# R-2R_Ladder_V2.net
KiCad netlist of a schematic drawn in EasyEDA
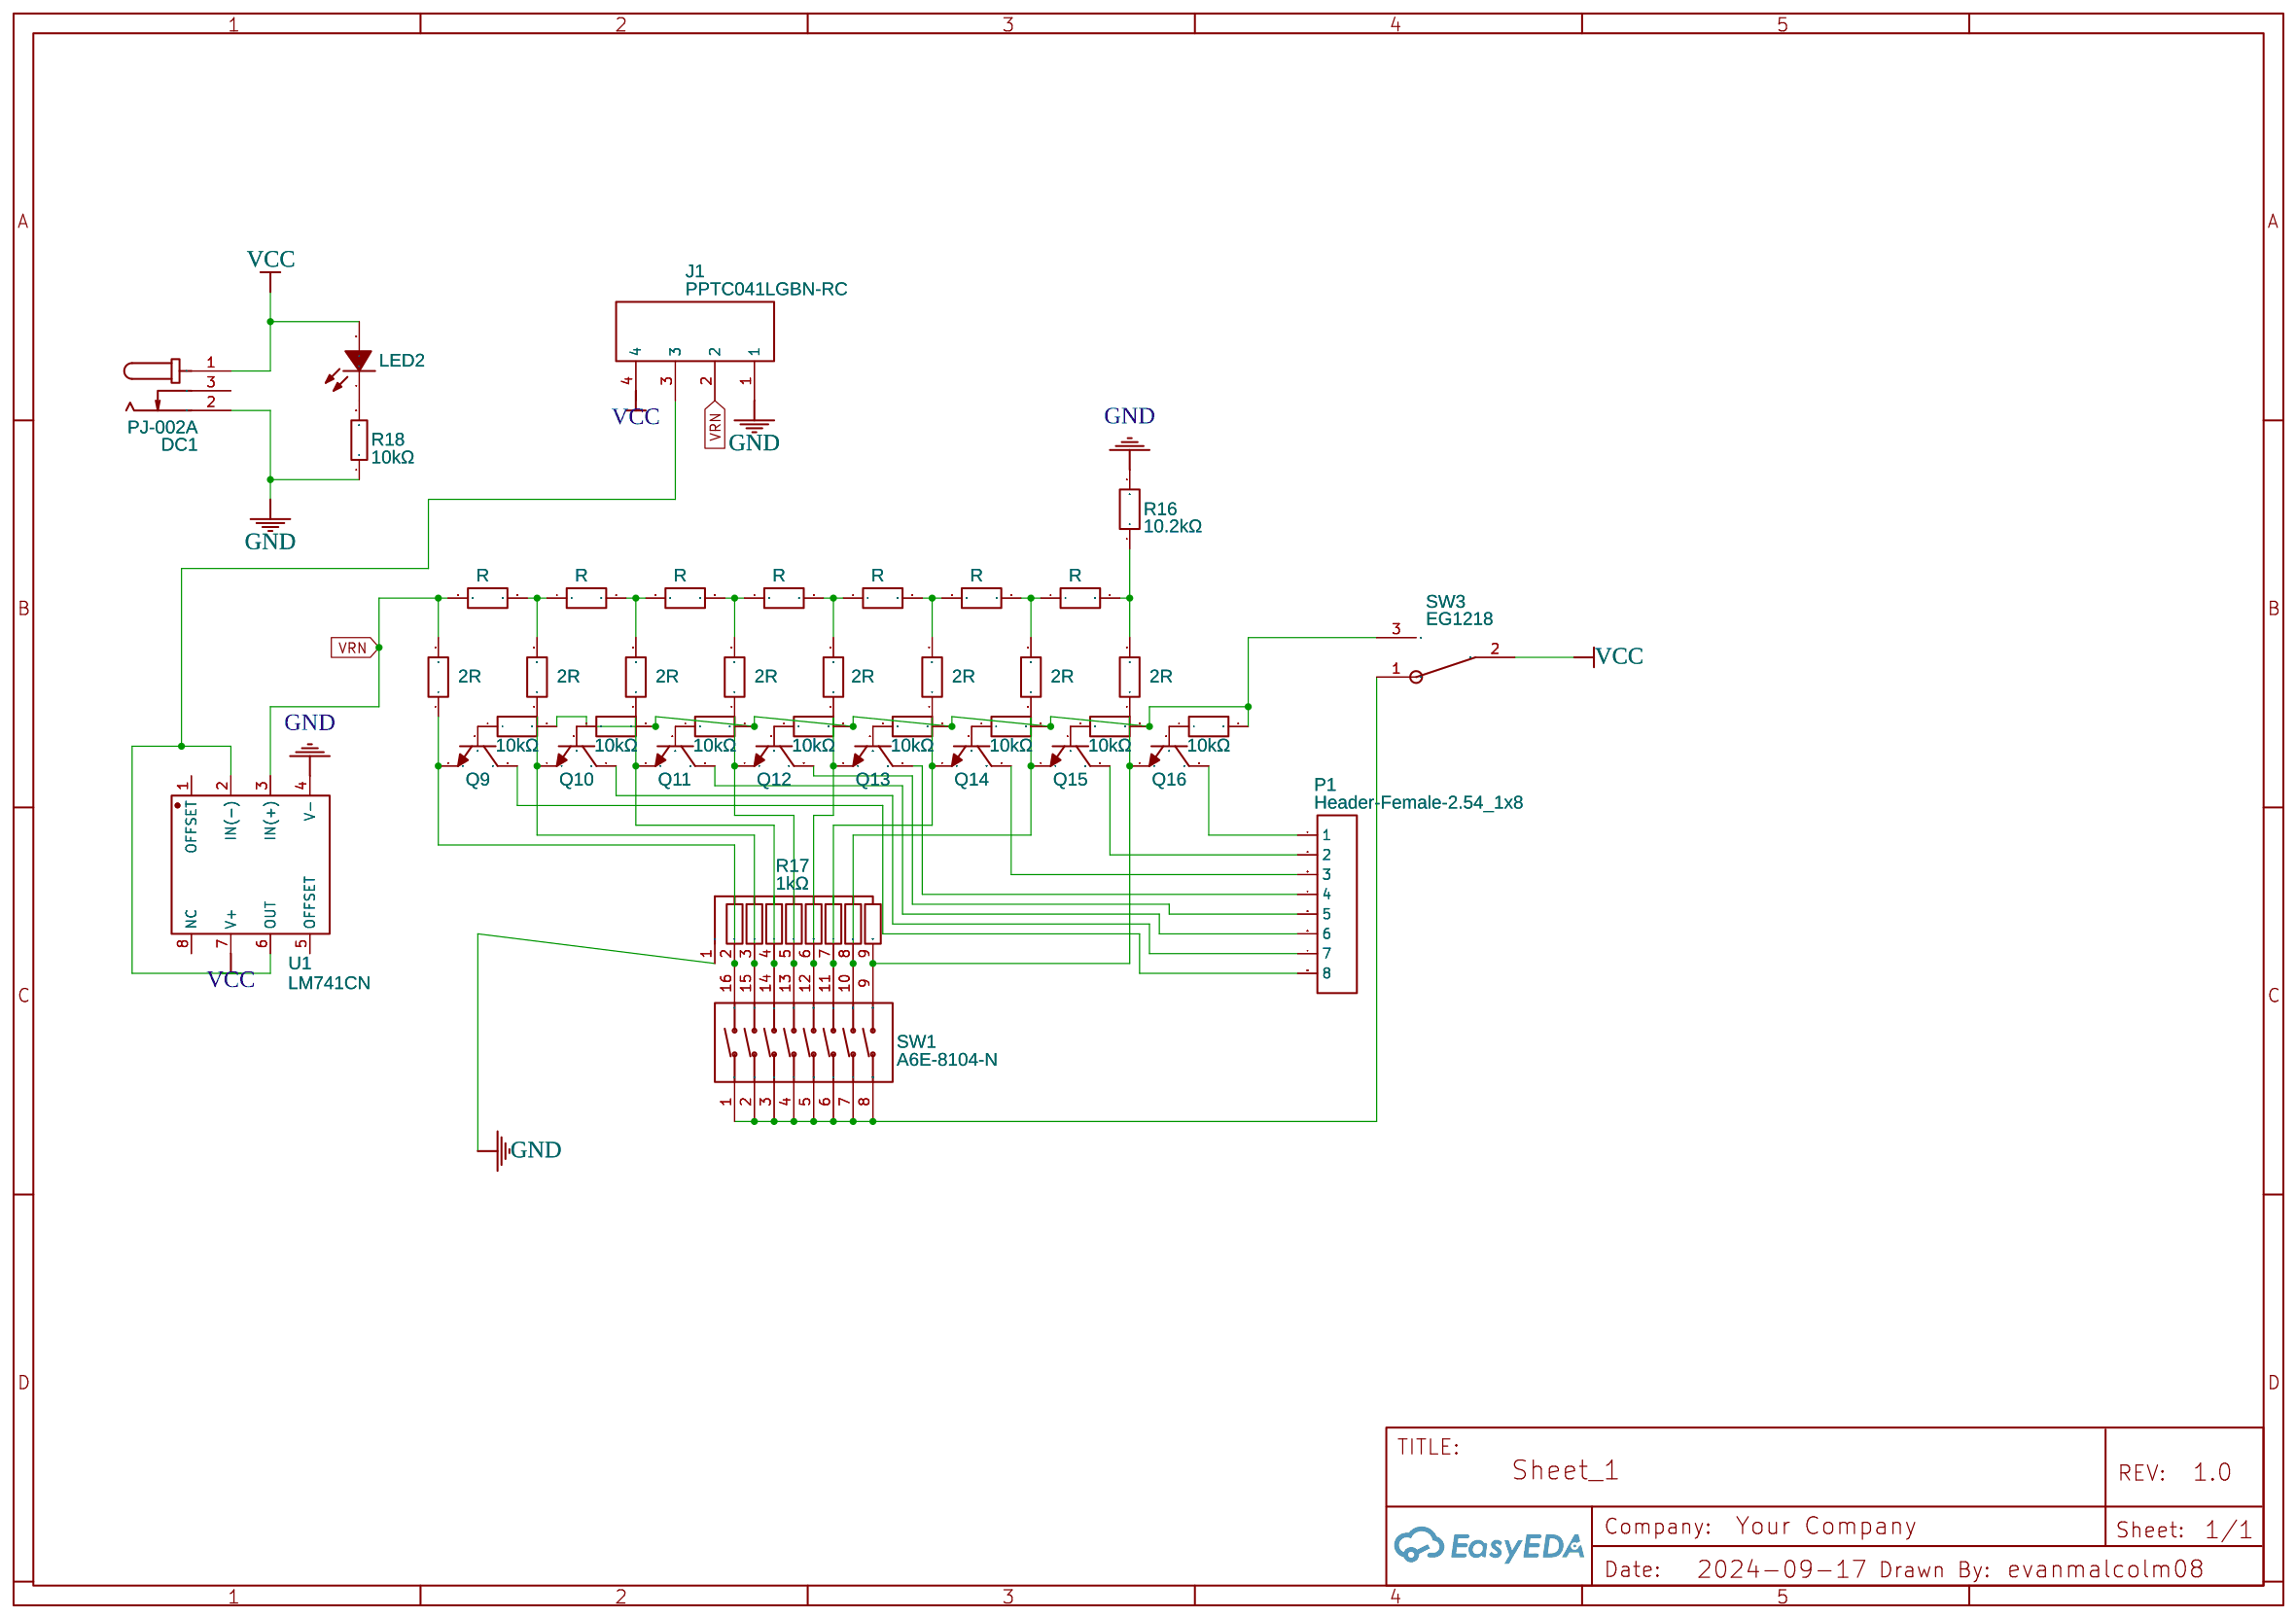
[diagram p0: schematic sheet]

(export (version "E")
  (design (tool "Eeschema 10.0.6"))
  (components
    (comp (ref "DC1")
      (value "PJ-002A")
      (fields (field (name "Manufacturer") "CUI"))
      (libsource (lib "") (part "PJ-002A"))
    )
    (comp (ref "J1") (value "PPTC041LGBN-RC") (libsource (lib "") (part "PPTC041LGBN-RC")))
    (comp (ref "LED2")
      (value "LTST-C150TBKT")
      (fields (field (name "Manufacturer") "LITEON(光宝)"))
      (libsource (lib "") (part "LTST-C150TBKT"))
    )
    (comp (ref "P1")
      (value "Header-Female-2.54_1x8")
      (fields (field (name "Manufacturer Part") "2.54-1*8P母环保") (field (name "Manufacturer") "BOOMELE(博穆精密)"))
      (libsource (lib "") (part "Header-Female-2.54_1x8"))
    )
    (comp (ref "Q9")
      (value "2N3904TF")
      (fields (field (name "Manufacturer") "onsemi(安森美)"))
      (libsource (lib "") (part "2N3904TF"))
    )
    (comp (ref "Q10")
      (value "2N3904TF")
      (fields (field (name "Manufacturer") "onsemi(安森美)"))
      (libsource (lib "") (part "2N3904TF"))
    )
    (comp (ref "Q11")
      (value "2N3904TF")
      (fields (field (name "Manufacturer") "onsemi(安森美)"))
      (libsource (lib "") (part "2N3904TF"))
    )
    (comp (ref "Q12")
      (value "2N3904TF")
      (fields (field (name "Manufacturer") "onsemi(安森美)"))
      (libsource (lib "") (part "2N3904TF"))
    )
    (comp (ref "Q13")
      (value "2N3904TF")
      (fields (field (name "Manufacturer") "onsemi(安森美)"))
      (libsource (lib "") (part "2N3904TF"))
    )
    (comp (ref "Q14")
      (value "2N3904TF")
      (fields (field (name "Manufacturer") "onsemi(安森美)"))
      (libsource (lib "") (part "2N3904TF"))
    )
    (comp (ref "Q15")
      (value "2N3904TF")
      (fields (field (name "Manufacturer") "onsemi(安森美)"))
      (libsource (lib "") (part "2N3904TF"))
    )
    (comp (ref "Q16")
      (value "2N3904TF")
      (fields (field (name "Manufacturer") "onsemi(安森美)"))
      (libsource (lib "") (part "2N3904TF"))
    )
    (comp (ref "R1")
      (value "R")
      (fields
        (field (name "Manufacturer Part") "CF14JT10K0")
        (field (name "Manufacturer") "SEI(Stackpole Electronics Inc.)")
      )
      (libsource (lib "") (part "CF14JT10K0"))
    )
    (comp (ref "R2")
      (value "R")
      (fields
        (field (name "Manufacturer Part") "CF14JT10K0")
        (field (name "Manufacturer") "SEI(Stackpole Electronics Inc.)")
      )
      (libsource (lib "") (part "CF14JT10K0"))
    )
    (comp (ref "R3")
      (value "R")
      (fields
        (field (name "Manufacturer Part") "CF14JT10K0")
        (field (name "Manufacturer") "SEI(Stackpole Electronics Inc.)")
      )
      (libsource (lib "") (part "CF14JT10K0"))
    )
    (comp (ref "R4")
      (value "R")
      (fields
        (field (name "Manufacturer Part") "CF14JT10K0")
        (field (name "Manufacturer") "SEI(Stackpole Electronics Inc.)")
      )
      (libsource (lib "") (part "CF14JT10K0"))
    )
    (comp (ref "R5")
      (value "R")
      (fields
        (field (name "Manufacturer Part") "CF14JT10K0")
        (field (name "Manufacturer") "SEI(Stackpole Electronics Inc.)")
      )
      (libsource (lib "") (part "CF14JT10K0"))
    )
    (comp (ref "R6")
      (value "R")
      (fields
        (field (name "Manufacturer Part") "CF14JT10K0")
        (field (name "Manufacturer") "SEI(Stackpole Electronics Inc.)")
      )
      (libsource (lib "") (part "CF14JT10K0"))
    )
    (comp (ref "R7")
      (value "R")
      (fields
        (field (name "Manufacturer Part") "CF14JT10K0")
        (field (name "Manufacturer") "SEI(Stackpole Electronics Inc.)")
      )
      (libsource (lib "") (part "CF14JT10K0"))
    )
    (comp (ref "R8")
      (value "2R")
      (fields
        (field (name "Manufacturer Part") "CF14JT10K0")
        (field (name "Manufacturer") "SEI(Stackpole Electronics Inc.)")
      )
      (libsource (lib "") (part "CF14JT10K0_1"))
    )
    (comp (ref "R9")
      (value "2R")
      (fields
        (field (name "Manufacturer Part") "CF14JT10K0")
        (field (name "Manufacturer") "SEI(Stackpole Electronics Inc.)")
      )
      (libsource (lib "") (part "CF14JT10K0_1"))
    )
    (comp (ref "R10")
      (value "2R")
      (fields
        (field (name "Manufacturer Part") "CF14JT10K0")
        (field (name "Manufacturer") "SEI(Stackpole Electronics Inc.)")
      )
      (libsource (lib "") (part "CF14JT10K0_1"))
    )
    (comp (ref "R11")
      (value "2R")
      (fields
        (field (name "Manufacturer Part") "CF14JT10K0")
        (field (name "Manufacturer") "SEI(Stackpole Electronics Inc.)")
      )
      (libsource (lib "") (part "CF14JT10K0_1"))
    )
    (comp (ref "R12")
      (value "2R")
      (fields
        (field (name "Manufacturer Part") "CF14JT10K0")
        (field (name "Manufacturer") "SEI(Stackpole Electronics Inc.)")
      )
      (libsource (lib "") (part "CF14JT10K0_1"))
    )
    (comp (ref "R13")
      (value "2R")
      (fields
        (field (name "Manufacturer Part") "CF14JT10K0")
        (field (name "Manufacturer") "SEI(Stackpole Electronics Inc.)")
      )
      (libsource (lib "") (part "CF14JT10K0_1"))
    )
    (comp (ref "R14")
      (value "2R")
      (fields
        (field (name "Manufacturer Part") "CF14JT10K0")
        (field (name "Manufacturer") "SEI(Stackpole Electronics Inc.)")
      )
      (libsource (lib "") (part "CF14JT10K0_1"))
    )
    (comp (ref "R15")
      (value "2R")
      (fields
        (field (name "Manufacturer Part") "CF14JT10K0")
        (field (name "Manufacturer") "SEI(Stackpole Electronics Inc.)")
      )
      (libsource (lib "") (part "CF14JT10K0_1"))
    )
    (comp (ref "R16")
      (value "10.2kΩ")
      (fields
        (field (name "Manufacturer Part") "CF14JT10K0")
        (field (name "Manufacturer") "SEI(Stackpole Electronics Inc.)")
      )
      (libsource (lib "") (part "CF14JT10K0_1"))
    )
    (comp (ref "R17")
      (value "1kΩ")
      (fields (field (name "Manufacturer Part") "4609X-101-102LF") (field (name "Manufacturer") "BOURNS"))
      (libsource (lib "") (part "4609X-101-102LF"))
    )
    (comp (ref "R18")
      (value "10kΩ")
      (fields (field (name "Manufacturer Part") "CR1206-FX-1002ELF") (field (name "Manufacturer") "BOURNS"))
      (libsource (lib "") (part "CR1206-FX-1002ELF"))
    )
    (comp (ref "R27")
      (value "10kΩ")
      (fields
        (field (name "Manufacturer Part") "CF14JT10K0")
        (field (name "Manufacturer") "SEI(Stackpole Electronics Inc.)")
      )
      (libsource (lib "") (part "CF14JT10K0"))
    )
    (comp (ref "R28")
      (value "10kΩ")
      (fields
        (field (name "Manufacturer Part") "CF14JT10K0")
        (field (name "Manufacturer") "SEI(Stackpole Electronics Inc.)")
      )
      (libsource (lib "") (part "CF14JT10K0"))
    )
    (comp (ref "R29")
      (value "10kΩ")
      (fields
        (field (name "Manufacturer Part") "CF14JT10K0")
        (field (name "Manufacturer") "SEI(Stackpole Electronics Inc.)")
      )
      (libsource (lib "") (part "CF14JT10K0"))
    )
    (comp (ref "R30")
      (value "10kΩ")
      (fields
        (field (name "Manufacturer Part") "CF14JT10K0")
        (field (name "Manufacturer") "SEI(Stackpole Electronics Inc.)")
      )
      (libsource (lib "") (part "CF14JT10K0"))
    )
    (comp (ref "R31")
      (value "10kΩ")
      (fields
        (field (name "Manufacturer Part") "CF14JT10K0")
        (field (name "Manufacturer") "SEI(Stackpole Electronics Inc.)")
      )
      (libsource (lib "") (part "CF14JT10K0"))
    )
    (comp (ref "R32")
      (value "10kΩ")
      (fields
        (field (name "Manufacturer Part") "CF14JT10K0")
        (field (name "Manufacturer") "SEI(Stackpole Electronics Inc.)")
      )
      (libsource (lib "") (part "CF14JT10K0"))
    )
    (comp (ref "R33")
      (value "10kΩ")
      (fields
        (field (name "Manufacturer Part") "CF14JT10K0")
        (field (name "Manufacturer") "SEI(Stackpole Electronics Inc.)")
      )
      (libsource (lib "") (part "CF14JT10K0"))
    )
    (comp (ref "R34")
      (value "10kΩ")
      (fields
        (field (name "Manufacturer Part") "CF14JT10K0")
        (field (name "Manufacturer") "SEI(Stackpole Electronics Inc.)")
      )
      (libsource (lib "") (part "CF14JT10K0"))
    )
    (comp (ref "SW1")
      (value "A6E-8104-N")
      (fields (field (name "Manufacturer") "OMRON(欧姆龙)"))
      (libsource (lib "") (part "A6E-8104-N"))
    )
    (comp (ref "SW3")
      (value "EG1218")
      (fields (field (name "Manufacturer") "E-Switch"))
      (libsource (lib "") (part "EG1218"))
    )
    (comp (ref "U1")
      (value "LM741CN")
      (fields (field (name "Manufacturer Part") "LM741CN/NOPB") (field (name "Manufacturer") "TI(德州仪器)"))
      (libsource (lib "") (part "LM741CN"))
    )
  )
  (nets
    (net (code "1") (name "GND") (class "Default")
      (node (ref "DC1") (pin "2") (pinfunction "2_2") (pintype "unspecified"))
      (node (ref "J1") (pin "1") (pinfunction "1_1") (pintype "unspecified"))
      (node (ref "R16") (pin "2") (pinfunction "2_2") (pintype "unspecified"))
      (node (ref "R17") (pin "1") (pinfunction "1_1") (pintype "unspecified"))
      (node (ref "R18") (pin "1") (pinfunction "1_1") (pintype "unspecified"))
      (node (ref "U1") (pin "4") (pinfunction "V-_4") (pintype "unspecified"))
    )
    (net (code "2") (name "Net-(LED2-K)") (class "Default")
      (node (ref "LED2") (pin "1") (pinfunction "K_1") (pintype "unspecified"))
      (node (ref "R18") (pin "2") (pinfunction "2_2") (pintype "unspecified"))
    )
    (net (code "3") (name "Net-(Q9-B)") (class "Default")
      (node (ref "Q9") (pin "2") (pinfunction "B_2") (pintype "input"))
      (node (ref "R34") (pin "1") (pinfunction "1_1") (pintype "unspecified"))
    )
    (net (code "4") (name "Net-(Q9-C)") (class "Default")
      (node (ref "P1") (pin "8") (pinfunction "8_8") (pintype "input"))
      (node (ref "Q9") (pin "3") (pinfunction "C_3") (pintype "input"))
    )
    (net (code "5") (name "Net-(Q9-E)") (class "Default")
      (node (ref "Q9") (pin "1") (pinfunction "E_1") (pintype "input"))
      (node (ref "R17") (pin "2") (pinfunction "2_2") (pintype "unspecified"))
      (node (ref "R8") (pin "1") (pinfunction "1_1") (pintype "unspecified"))
      (node (ref "SW1") (pin "16") (pinfunction "16_16") (pintype "unspecified"))
    )
    (net (code "6") (name "Net-(Q10-B)") (class "Default")
      (node (ref "Q10") (pin "2") (pinfunction "B_2") (pintype "input"))
      (node (ref "R33") (pin "1") (pinfunction "1_1") (pintype "unspecified"))
    )
    (net (code "7") (name "Net-(Q10-C)") (class "Default")
      (node (ref "P1") (pin "7") (pinfunction "7_7") (pintype "input"))
      (node (ref "Q10") (pin "3") (pinfunction "C_3") (pintype "input"))
    )
    (net (code "8") (name "Net-(Q10-E)") (class "Default")
      (node (ref "Q10") (pin "1") (pinfunction "E_1") (pintype "input"))
      (node (ref "R17") (pin "3") (pinfunction "3_3") (pintype "unspecified"))
      (node (ref "R9") (pin "1") (pinfunction "1_1") (pintype "unspecified"))
      (node (ref "SW1") (pin "15") (pinfunction "15_15") (pintype "unspecified"))
    )
    (net (code "9") (name "Net-(Q11-B)") (class "Default")
      (node (ref "Q11") (pin "2") (pinfunction "B_2") (pintype "input"))
      (node (ref "R32") (pin "1") (pinfunction "1_1") (pintype "unspecified"))
    )
    (net (code "10") (name "Net-(Q11-C)") (class "Default")
      (node (ref "P1") (pin "6") (pinfunction "6_6") (pintype "input"))
      (node (ref "Q11") (pin "3") (pinfunction "C_3") (pintype "input"))
    )
    (net (code "11") (name "Net-(Q11-E)") (class "Default")
      (node (ref "Q11") (pin "1") (pinfunction "E_1") (pintype "input"))
      (node (ref "R10") (pin "1") (pinfunction "1_1") (pintype "unspecified"))
      (node (ref "R17") (pin "4") (pinfunction "4_4") (pintype "unspecified"))
      (node (ref "SW1") (pin "14") (pinfunction "14_14") (pintype "unspecified"))
    )
    (net (code "12") (name "Net-(Q12-B)") (class "Default")
      (node (ref "Q12") (pin "2") (pinfunction "B_2") (pintype "input"))
      (node (ref "R31") (pin "1") (pinfunction "1_1") (pintype "unspecified"))
    )
    (net (code "13") (name "Net-(Q12-C)") (class "Default")
      (node (ref "P1") (pin "5") (pinfunction "5_5") (pintype "input"))
      (node (ref "Q12") (pin "3") (pinfunction "C_3") (pintype "input"))
    )
    (net (code "14") (name "Net-(Q12-E)") (class "Default")
      (node (ref "Q12") (pin "1") (pinfunction "E_1") (pintype "input"))
      (node (ref "R11") (pin "1") (pinfunction "1_1") (pintype "unspecified"))
      (node (ref "R17") (pin "5") (pinfunction "5_5") (pintype "unspecified"))
      (node (ref "SW1") (pin "13") (pinfunction "13_13") (pintype "unspecified"))
    )
    (net (code "15") (name "Net-(Q13-B)") (class "Default")
      (node (ref "Q13") (pin "2") (pinfunction "B_2") (pintype "input"))
      (node (ref "R30") (pin "1") (pinfunction "1_1") (pintype "unspecified"))
    )
    (net (code "16") (name "Net-(Q13-C)") (class "Default")
      (node (ref "P1") (pin "4") (pinfunction "4_4") (pintype "input"))
      (node (ref "Q13") (pin "3") (pinfunction "C_3") (pintype "input"))
    )
    (net (code "17") (name "Net-(Q13-E)") (class "Default")
      (node (ref "Q13") (pin "1") (pinfunction "E_1") (pintype "input"))
      (node (ref "R12") (pin "1") (pinfunction "1_1") (pintype "unspecified"))
      (node (ref "R17") (pin "6") (pinfunction "6_6") (pintype "unspecified"))
      (node (ref "SW1") (pin "12") (pinfunction "12_12") (pintype "unspecified"))
    )
    (net (code "18") (name "Net-(Q14-B)") (class "Default")
      (node (ref "Q14") (pin "2") (pinfunction "B_2") (pintype "input"))
      (node (ref "R29") (pin "1") (pinfunction "1_1") (pintype "unspecified"))
    )
    (net (code "19") (name "Net-(Q14-C)") (class "Default")
      (node (ref "P1") (pin "3") (pinfunction "3_3") (pintype "input"))
      (node (ref "Q14") (pin "3") (pinfunction "C_3") (pintype "input"))
    )
    (net (code "20") (name "Net-(Q14-E)") (class "Default")
      (node (ref "Q14") (pin "1") (pinfunction "E_1") (pintype "input"))
      (node (ref "R13") (pin "1") (pinfunction "1_1") (pintype "unspecified"))
      (node (ref "R17") (pin "7") (pinfunction "7_7") (pintype "unspecified"))
      (node (ref "SW1") (pin "11") (pinfunction "11_11") (pintype "unspecified"))
    )
    (net (code "21") (name "Net-(Q15-B)") (class "Default")
      (node (ref "Q15") (pin "2") (pinfunction "B_2") (pintype "input"))
      (node (ref "R28") (pin "1") (pinfunction "1_1") (pintype "unspecified"))
    )
    (net (code "22") (name "Net-(Q15-C)") (class "Default")
      (node (ref "P1") (pin "2") (pinfunction "2_2") (pintype "input"))
      (node (ref "Q15") (pin "3") (pinfunction "C_3") (pintype "input"))
    )
    (net (code "23") (name "Net-(Q15-E)") (class "Default")
      (node (ref "Q15") (pin "1") (pinfunction "E_1") (pintype "input"))
      (node (ref "R14") (pin "1") (pinfunction "1_1") (pintype "unspecified"))
      (node (ref "R17") (pin "8") (pinfunction "8_8") (pintype "unspecified"))
      (node (ref "SW1") (pin "10") (pinfunction "10_10") (pintype "unspecified"))
    )
    (net (code "24") (name "Net-(Q16-B)") (class "Default")
      (node (ref "Q16") (pin "2") (pinfunction "B_2") (pintype "input"))
      (node (ref "R27") (pin "1") (pinfunction "1_1") (pintype "unspecified"))
    )
    (net (code "25") (name "Net-(Q16-C)") (class "Default")
      (node (ref "P1") (pin "1") (pinfunction "1_1") (pintype "input"))
      (node (ref "Q16") (pin "3") (pinfunction "C_3") (pintype "input"))
    )
    (net (code "26") (name "Net-(Q16-E)") (class "Default")
      (node (ref "Q16") (pin "1") (pinfunction "E_1") (pintype "input"))
      (node (ref "R15") (pin "1") (pinfunction "1_1") (pintype "unspecified"))
      (node (ref "R17") (pin "9") (pinfunction "9_9") (pintype "unspecified"))
      (node (ref "SW1") (pin "9") (pinfunction "9_9") (pintype "unspecified"))
    )
    (net (code "27") (name "Net-(R1-Pad2)") (class "Default")
      (node (ref "R1") (pin "2") (pinfunction "2_2") (pintype "unspecified"))
      (node (ref "R2") (pin "1") (pinfunction "1_1") (pintype "unspecified"))
      (node (ref "R9") (pin "2") (pinfunction "2_2") (pintype "unspecified"))
    )
    (net (code "28") (name "Net-(R10-Pad2)") (class "Default")
      (node (ref "R10") (pin "2") (pinfunction "2_2") (pintype "unspecified"))
      (node (ref "R2") (pin "2") (pinfunction "2_2") (pintype "unspecified"))
      (node (ref "R3") (pin "1") (pinfunction "1_1") (pintype "unspecified"))
    )
    (net (code "29") (name "Net-(R11-Pad2)") (class "Default")
      (node (ref "R11") (pin "2") (pinfunction "2_2") (pintype "unspecified"))
      (node (ref "R3") (pin "2") (pinfunction "2_2") (pintype "unspecified"))
      (node (ref "R4") (pin "1") (pinfunction "1_1") (pintype "unspecified"))
    )
    (net (code "30") (name "Net-(R12-Pad2)") (class "Default")
      (node (ref "R12") (pin "2") (pinfunction "2_2") (pintype "unspecified"))
      (node (ref "R4") (pin "2") (pinfunction "2_2") (pintype "unspecified"))
      (node (ref "R5") (pin "1") (pinfunction "1_1") (pintype "unspecified"))
    )
    (net (code "31") (name "Net-(R13-Pad2)") (class "Default")
      (node (ref "R13") (pin "2") (pinfunction "2_2") (pintype "unspecified"))
      (node (ref "R5") (pin "2") (pinfunction "2_2") (pintype "unspecified"))
      (node (ref "R6") (pin "1") (pinfunction "1_1") (pintype "unspecified"))
    )
    (net (code "32") (name "Net-(R14-Pad2)") (class "Default")
      (node (ref "R14") (pin "2") (pinfunction "2_2") (pintype "unspecified"))
      (node (ref "R6") (pin "2") (pinfunction "2_2") (pintype "unspecified"))
      (node (ref "R7") (pin "1") (pinfunction "1_1") (pintype "unspecified"))
    )
    (net (code "33") (name "Net-(R15-Pad2)") (class "Default")
      (node (ref "R15") (pin "2") (pinfunction "2_2") (pintype "unspecified"))
      (node (ref "R16") (pin "1") (pinfunction "1_1") (pintype "unspecified"))
      (node (ref "R7") (pin "2") (pinfunction "2_2") (pintype "unspecified"))
    )
    (net (code "34") (name "Net-(R27-Pad2)") (class "Default")
      (node (ref "R27") (pin "2") (pinfunction "2_2") (pintype "unspecified"))
      (node (ref "R28") (pin "2") (pinfunction "2_2") (pintype "unspecified"))
      (node (ref "R29") (pin "2") (pinfunction "2_2") (pintype "unspecified"))
      (node (ref "R30") (pin "2") (pinfunction "2_2") (pintype "unspecified"))
      (node (ref "R31") (pin "2") (pinfunction "2_2") (pintype "unspecified"))
      (node (ref "R32") (pin "2") (pinfunction "2_2") (pintype "unspecified"))
      (node (ref "R33") (pin "2") (pinfunction "2_2") (pintype "unspecified"))
      (node (ref "R34") (pin "2") (pinfunction "2_2") (pintype "unspecified"))
      (node (ref "SW3") (pin "3") (pinfunction "3_3") (pintype "input"))
    )
    (net (code "35") (name "Net-(SW1-Pad1)") (class "Default")
      (node (ref "SW1") (pin "1") (pinfunction "1_1") (pintype "unspecified"))
      (node (ref "SW1") (pin "2") (pinfunction "2_2") (pintype "unspecified"))
      (node (ref "SW1") (pin "3") (pinfunction "3_3") (pintype "unspecified"))
      (node (ref "SW1") (pin "4") (pinfunction "4_4") (pintype "unspecified"))
      (node (ref "SW1") (pin "5") (pinfunction "5_5") (pintype "unspecified"))
      (node (ref "SW1") (pin "6") (pinfunction "6_6") (pintype "unspecified"))
      (node (ref "SW1") (pin "7") (pinfunction "7_7") (pintype "unspecified"))
      (node (ref "SW1") (pin "8") (pinfunction "8_8") (pintype "unspecified"))
      (node (ref "SW3") (pin "1") (pinfunction "1_1") (pintype "input"))
    )
    (net (code "36") (name "Net-(U1-IN(-))") (class "Default")
      (node (ref "J1") (pin "3") (pinfunction "3_3") (pintype "unspecified"))
      (node (ref "U1") (pin "2") (pinfunction "IN(-)_2") (pintype "unspecified"))
      (node (ref "U1") (pin "6") (pinfunction "OUT_6") (pintype "unspecified"))
    )
    (net (code "37") (name "VCC") (class "Default")
      (node (ref "DC1") (pin "1") (pinfunction "1_1") (pintype "unspecified"))
      (node (ref "LED2") (pin "2") (pinfunction "A_2") (pintype "unspecified"))
      (node (ref "SW3") (pin "2") (pinfunction "2_2") (pintype "input"))
      (node (ref "U1") (pin "7") (pinfunction "V+_7") (pintype "unspecified"))
    )
    (net (code "38") (name "VRN") (class "Default")
      (node (ref "J1") (pin "2") (pinfunction "2_2") (pintype "unspecified"))
      (node (ref "R1") (pin "1") (pinfunction "1_1") (pintype "unspecified"))
      (node (ref "R8") (pin "2") (pinfunction "2_2") (pintype "unspecified"))
      (node (ref "U1") (pin "3") (pinfunction "IN(+)_3") (pintype "unspecified"))
    )
    (net (code "39") (name "unconnected-(DC1-Pad3)") (class "Default")
      (node (ref "DC1") (pin "3") (pinfunction "3_3") (pintype "unspecified"))
    )
    (net (code "40") (name "unconnected-(J1-Pad4)") (class "Default")
      (node (ref "J1") (pin "4") (pinfunction "4_4") (pintype "unspecified"))
    )
    (net (code "41") (name "unconnected-(U1-NC-Pad8)") (class "Default")
      (node (ref "U1") (pin "8") (pinfunction "NC_8") (pintype "unspecified"))
    )
    (net (code "42") (name "unconnected-(U1-OFFSET-Pad1)") (class "Default")
      (node (ref "U1") (pin "1") (pinfunction "OFFSET_1") (pintype "unspecified"))
    )
    (net (code "43") (name "unconnected-(U1-OFFSET-Pad5)") (class "Default")
      (node (ref "U1") (pin "5") (pinfunction "OFFSET_5") (pintype "unspecified"))
    )
  )
)
